# o_clone_rev_fi2.net
KiCad netlist of a schematic drawn in EAGLE
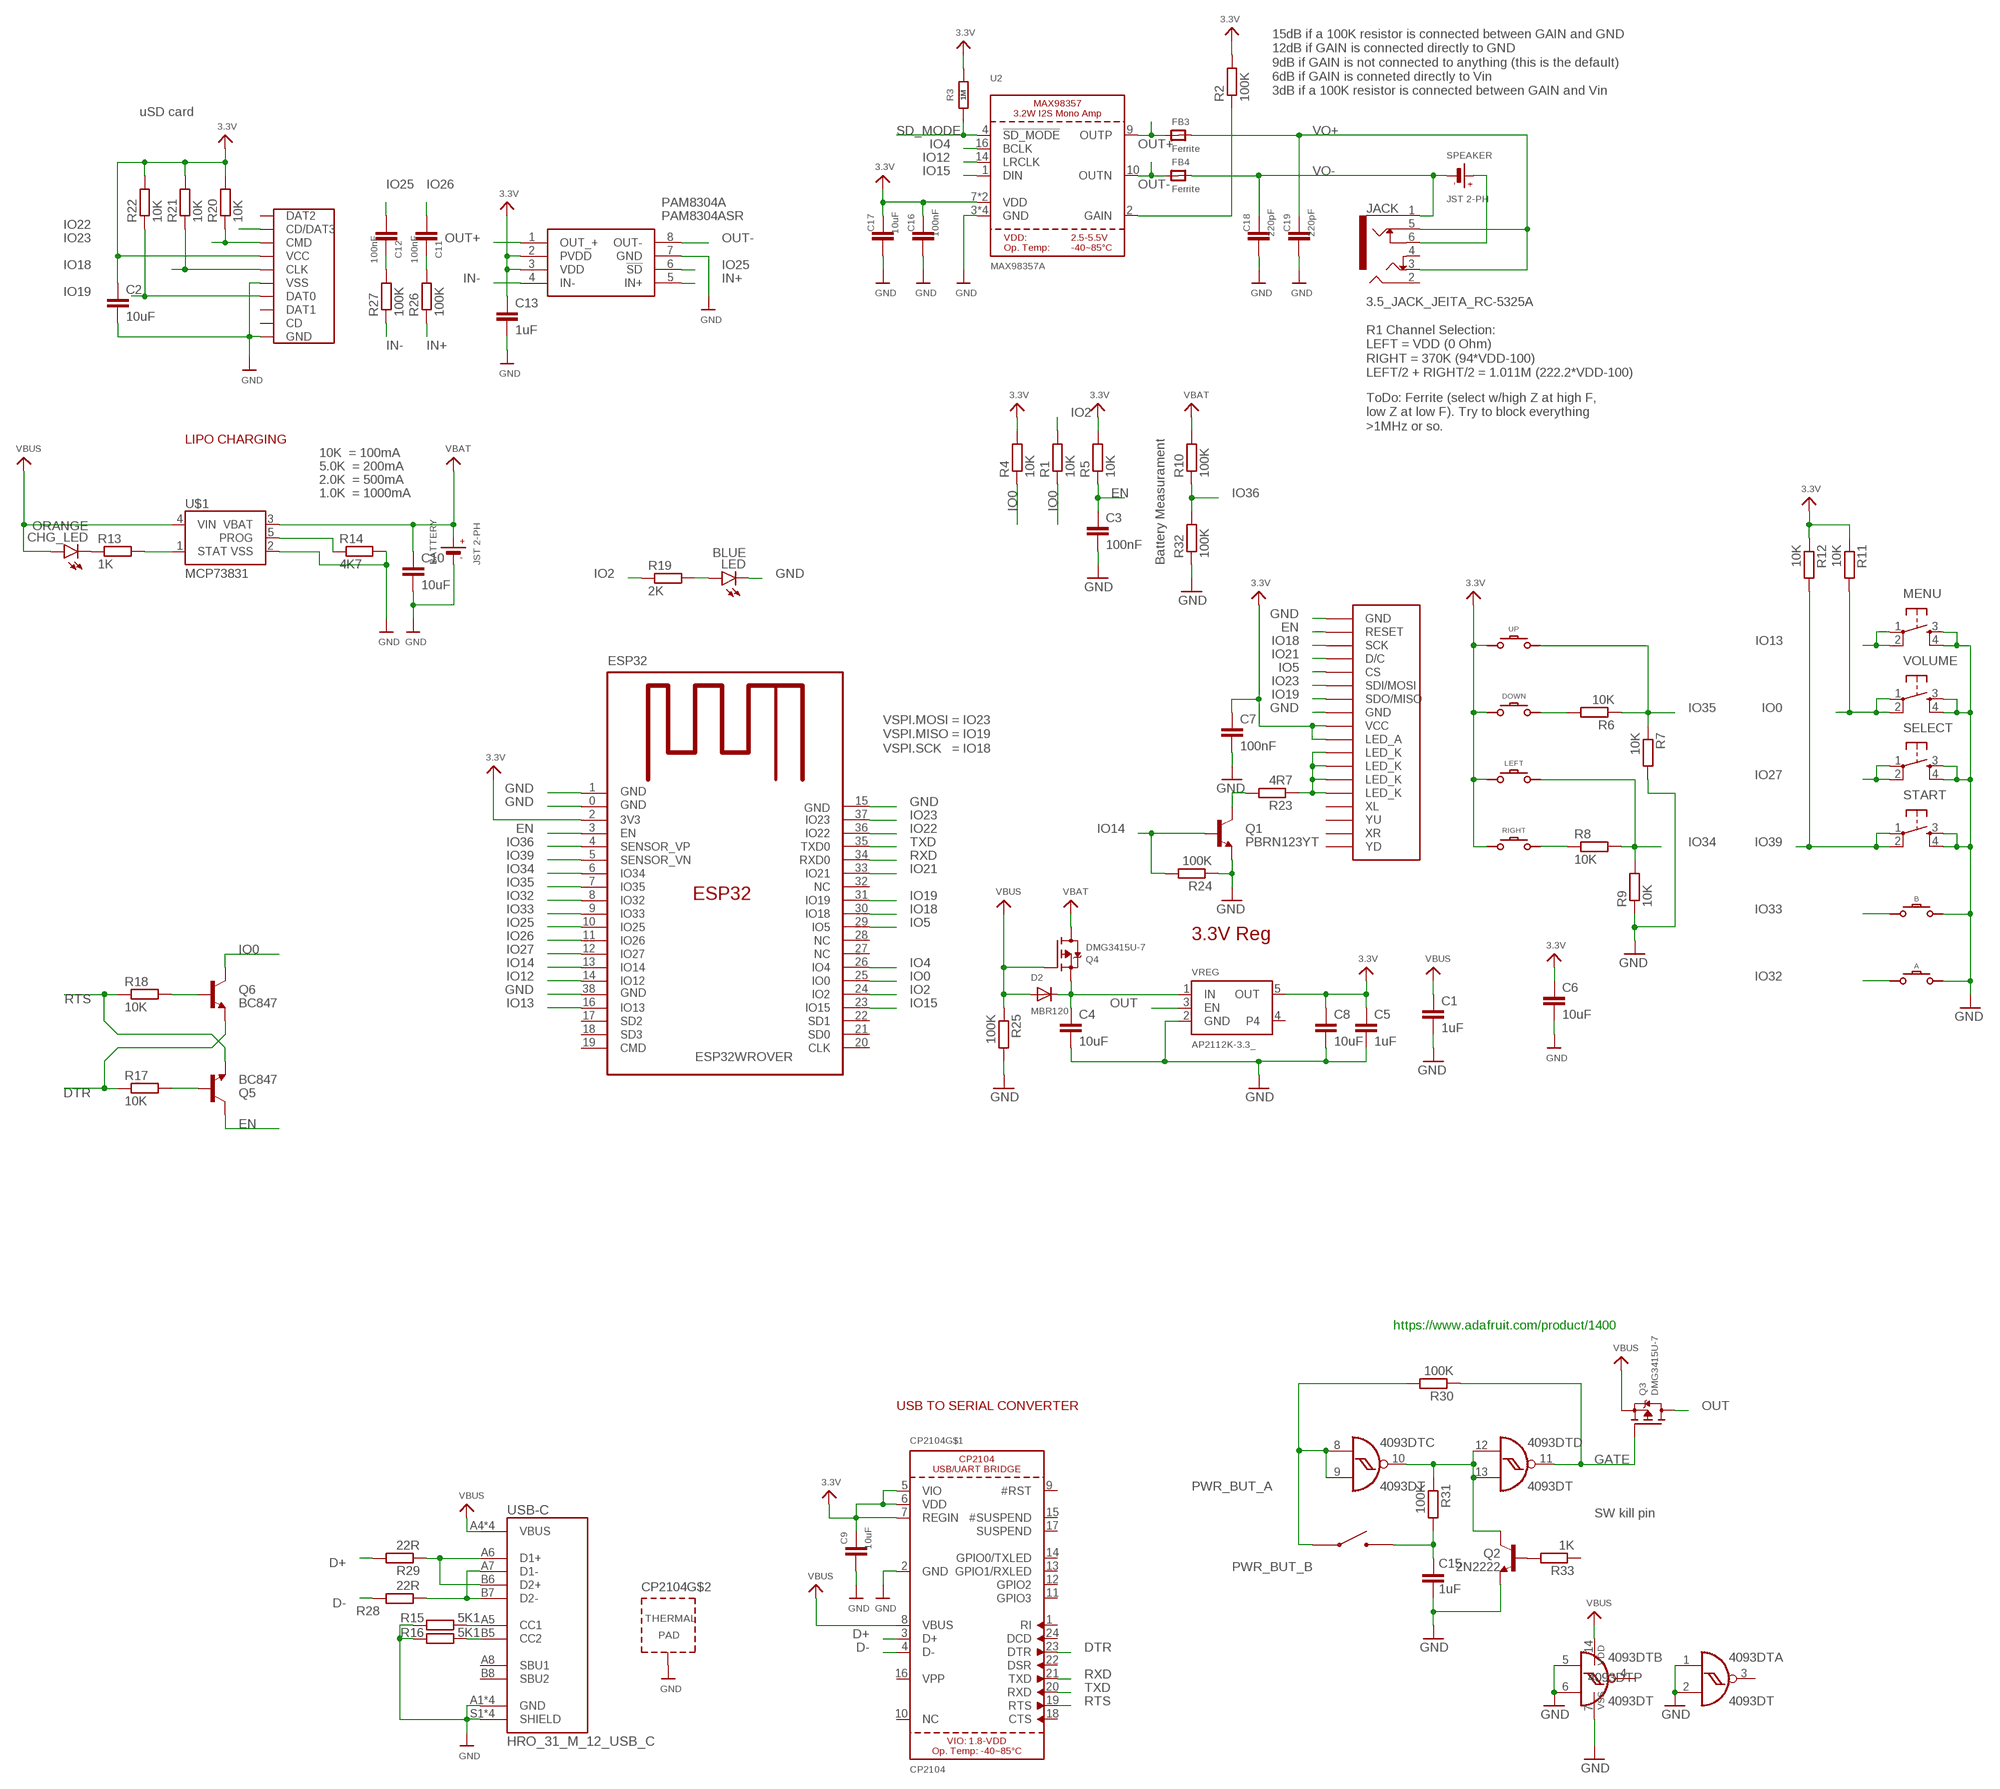
[diagram p0: schematic, sheet 1]

(export (version "E")
  (design (tool "Eeschema 10.0.6"))
  (components
    (comp (ref "4093DT")
      (value "4093DT")
      (footprint "eagle-import:MC14093B-TSSOP14")
      (libsource (lib "eagle-import") (part "4093DT"))
    )
    (comp (ref "A")
      (value "CONDUCTIVE_BUTTONCONDUCTIVE_BUTTON_THICK")
      (footprint "eagle-import:CONDUCTIVE_BUTTON_THICK")
      (libsource (lib "eagle-import") (part "CONDUCTIVE_BUTTONCONDUCTIVE_BUTTON_THICK"))
    )
    (comp (ref "B")
      (value "CONDUCTIVE_BUTTONCONDUCTIVE_BUTTON_THICK")
      (footprint "eagle-import:CONDUCTIVE_BUTTON_THICK")
      (libsource (lib "eagle-import") (part "CONDUCTIVE_BUTTONCONDUCTIVE_BUTTON_THICK"))
    )
    (comp (ref "BATTERY")
      (value "JST 2-PH")
      (footprint "eagle-import:JSTPH2")
      (libsource (lib "eagle-import") (part "JST_CONNECTOR"))
    )
    (comp (ref "C1")
      (value "1uF")
      (footprint "eagle-import:C0805")
      (libsource (lib "eagle-import") (part "C-EUC0805"))
    )
    (comp (ref "C2")
      (value "10uF")
      (footprint "eagle-import:C0805")
      (libsource (lib "eagle-import") (part "C-EUC0805"))
    )
    (comp (ref "C3")
      (value "100nF")
      (footprint "eagle-import:C0805")
      (libsource (lib "eagle-import") (part "C-EUC0805"))
    )
    (comp (ref "C4")
      (value "10uF")
      (footprint "eagle-import:C0805")
      (libsource (lib "eagle-import") (part "C-EUC0805"))
    )
    (comp (ref "C5")
      (value "1uF")
      (footprint "eagle-import:C0805")
      (libsource (lib "eagle-import") (part "C-EUC0805"))
    )
    (comp (ref "C6")
      (value "10uF")
      (footprint "eagle-import:C0805")
      (libsource (lib "eagle-import") (part "C-EUC0805"))
    )
    (comp (ref "C7")
      (value "100nF")
      (footprint "eagle-import:C0805")
      (libsource (lib "eagle-import") (part "C-EUC0805"))
    )
    (comp (ref "C8")
      (value "10uF")
      (footprint "eagle-import:C0805")
      (libsource (lib "eagle-import") (part "C-EUC0805"))
    )
    (comp (ref "C9")
      (value "10uF")
      (footprint "eagle-import:C0805")
      (libsource (lib "eagle-import") (part "C-EUC0805"))
    )
    (comp (ref "C10")
      (value "10uF")
      (footprint "eagle-import:C0805")
      (libsource (lib "eagle-import") (part "C-EUC0805"))
    )
    (comp (ref "C11")
      (value "100nF")
      (footprint "eagle-import:C0805")
      (libsource (lib "eagle-import") (part "C-EUC0805"))
    )
    (comp (ref "C12")
      (value "100nF")
      (footprint "eagle-import:C0805")
      (libsource (lib "eagle-import") (part "C-EUC0805"))
    )
    (comp (ref "C13")
      (value "1uF")
      (footprint "eagle-import:C0805")
      (libsource (lib "eagle-import") (part "C-EUC0805"))
    )
    (comp (ref "C15")
      (value "1uF")
      (footprint "eagle-import:C0805")
      (libsource (lib "eagle-import") (part "C-EUC0805"))
    )
    (comp (ref "C16")
      (value "100nF")
      (footprint "eagle-import:C0805")
      (libsource (lib "eagle-import") (part "C-EUC0805"))
    )
    (comp (ref "C17")
      (value "10uF")
      (footprint "eagle-import:C0805")
      (libsource (lib "eagle-import") (part "C-EUC0805"))
    )
    (comp (ref "C18")
      (value "220pF")
      (footprint "eagle-import:C0805")
      (libsource (lib "eagle-import") (part "C-EUC0805"))
    )
    (comp (ref "C19")
      (value "220pF")
      (footprint "eagle-import:C0805")
      (libsource (lib "eagle-import") (part "C-EUC0805"))
    )
    (comp (ref "CHG_LED")
      (value "ORANGE")
      (footprint "eagle-import:CHIPLED_0805")
      (libsource (lib "eagle-import") (part "LEDCHIPLED_0805"))
    )
    (comp (ref "CP2104")
      (value "CP2104")
      (footprint "eagle-import:QFN24_4MM_SMSC")
      (libsource (lib "eagle-import") (part "CP2104"))
    )
    (comp (ref "D2")
      (value "MBR120")
      (footprint "eagle-import:SOD-123")
      (libsource (lib "eagle-import") (part "DIODESOD-123"))
    )
    (comp (ref "DOWN")
      (value "CONDUCTIVE_BUTTONCONDUCTIVE_BUTTON_DIRECTIONAL_THICK")
      (footprint "eagle-import:CONDUCTIVE_BUTTON_DIRECTIONAL_THICK")
      (libsource (lib "eagle-import") (part "CONDUCTIVE_BUTTONCONDUCTIVE_BUTTON_DIRECTIONAL_THICK"))
    )
    (comp (ref "ESP32")
      (value "ESP32WROVER")
      (footprint "eagle-import:ESP32WROVER")
      (libsource (lib "eagle-import") (part "ESP32WROVER"))
    )
    (comp (ref "FB3")
      (value "Ferrite")
      (footprint "eagle-import:0805")
      (libsource (lib "eagle-import") (part "FERRITE0805"))
    )
    (comp (ref "FB4")
      (value "Ferrite")
      (footprint "eagle-import:0805")
      (libsource (lib "eagle-import") (part "FERRITE0805"))
    )
    (comp (ref "JACK")
      (value "3.5_JACK_JEITA_RC-5325A")
      (footprint "eagle-import:3.5_JACK_JEITA_RC-5325A")
      (libsource (lib "eagle-import") (part "3.5_JACK_JEITA_RC-5325A"))
    )
    (comp (ref "LCD")
      (value "ILI9341_3.2LCD_")
      (footprint "eagle-import:LI9341_3.2LCD")
      (libsource (lib "eagle-import") (part "ILI9341_3.2LCD_"))
    )
    (comp (ref "LED")
      (value "BLUE")
      (footprint "eagle-import:CHIPLED_0805")
      (libsource (lib "eagle-import") (part "LEDCHIPLED_0805"))
    )
    (comp (ref "LEFT")
      (value "CONDUCTIVE_BUTTONCONDUCTIVE_BUTTON_DIRECTIONAL_THICK")
      (footprint "eagle-import:CONDUCTIVE_BUTTON_DIRECTIONAL_THICK")
      (libsource (lib "eagle-import") (part "CONDUCTIVE_BUTTONCONDUCTIVE_BUTTON_DIRECTIONAL_THICK"))
    )
    (comp (ref "MENU")
      (value "TACTILE_SWITCHE_5X5_MICRO_")
      (footprint "eagle-import:TACTILE_SWITCH_5X5_MICRO")
      (libsource (lib "eagle-import") (part "TACTILE_SWITCHE_5X5_MICRO_"))
    )
    (comp (ref "PAM8304A")
      (value "PAM8304ASR")
      (footprint "eagle-import:SOP65P490X110-8N")
      (fields (field (name "MOUSER_PART_NUMBER") "621-PAM8304ASR"))
      (libsource (lib "eagle-import") (part "PAM8304ASR"))
    )
    (comp (ref "Q1")
      (value "PBRN123YT")
      (footprint "eagle-import:SOT23-3")
      (libsource (lib "eagle-import") (part "TRANSISTOR_NPNSOT23-3"))
    )
    (comp (ref "Q2")
      (value "2N2222")
      (footprint "eagle-import:SOT23-BEC")
      (libsource (lib "eagle-import") (part "-NPN-SOT23-BECMMBT2222ALT1"))
    )
    (comp (ref "Q3")
      (value "DMG3415U-7")
      (footprint "eagle-import:SOT23-WIDE")
      (libsource (lib "eagle-import") (part "MOSFET-PWIDE"))
    )
    (comp (ref "Q4")
      (value "DMG3415U-7")
      (footprint "eagle-import:SOT23-R")
      (libsource (lib "eagle-import") (part "MOSFET-P"))
    )
    (comp (ref "Q5")
      (value "BC847")
      (footprint "eagle-import:SOT23-3")
      (libsource (lib "eagle-import") (part "TRANSISTOR_NPNSOT23-3"))
    )
    (comp (ref "Q6")
      (value "BC847")
      (footprint "eagle-import:SOT23-3")
      (libsource (lib "eagle-import") (part "TRANSISTOR_NPNSOT23-3"))
    )
    (comp (ref "R1")
      (value "10K")
      (footprint "eagle-import:R0805")
      (libsource (lib "eagle-import") (part "R-EU_R0805"))
    )
    (comp (ref "R2")
      (value "100K")
      (footprint "eagle-import:R0805")
      (libsource (lib "eagle-import") (part "R-EU_R0805"))
    )
    (comp (ref "R3")
      (value "1M")
      (footprint "eagle-import:R0805")
      (libsource (lib "eagle-import") (part "R-EU_R0805"))
    )
    (comp (ref "R4")
      (value "10K")
      (footprint "eagle-import:R0805")
      (libsource (lib "eagle-import") (part "R-EU_R0805"))
    )
    (comp (ref "R5")
      (value "10K")
      (footprint "eagle-import:R0805")
      (libsource (lib "eagle-import") (part "R-EU_R0805"))
    )
    (comp (ref "R6")
      (value "10K")
      (footprint "eagle-import:R0805")
      (libsource (lib "eagle-import") (part "R-EU_R0805"))
    )
    (comp (ref "R7")
      (value "10K")
      (footprint "eagle-import:R0805")
      (libsource (lib "eagle-import") (part "R-EU_R0805"))
    )
    (comp (ref "R8")
      (value "10K")
      (footprint "eagle-import:R0805")
      (libsource (lib "eagle-import") (part "R-EU_R0805"))
    )
    (comp (ref "R9")
      (value "10K")
      (footprint "eagle-import:R0805")
      (libsource (lib "eagle-import") (part "R-EU_R0805"))
    )
    (comp (ref "R10")
      (value "100K")
      (footprint "eagle-import:R0805")
      (libsource (lib "eagle-import") (part "R-EU_R0805"))
    )
    (comp (ref "R11")
      (value "10K")
      (footprint "eagle-import:R0805")
      (libsource (lib "eagle-import") (part "R-EU_R0805"))
    )
    (comp (ref "R12")
      (value "10K")
      (footprint "eagle-import:R0805")
      (libsource (lib "eagle-import") (part "R-EU_R0805"))
    )
    (comp (ref "R13")
      (value "1K")
      (footprint "eagle-import:R0805")
      (libsource (lib "eagle-import") (part "R-EU_R0805"))
    )
    (comp (ref "R14")
      (value "4K7")
      (footprint "eagle-import:R0805")
      (libsource (lib "eagle-import") (part "R-EU_R0805"))
    )
    (comp (ref "R15")
      (value "5K1")
      (footprint "eagle-import:R0805")
      (libsource (lib "eagle-import") (part "R-EU_R0805"))
    )
    (comp (ref "R16")
      (value "5K1")
      (footprint "eagle-import:R0805")
      (libsource (lib "eagle-import") (part "R-EU_R0805"))
    )
    (comp (ref "R17")
      (value "10K")
      (footprint "eagle-import:R0805")
      (libsource (lib "eagle-import") (part "R-EU_R0805"))
    )
    (comp (ref "R18")
      (value "10K")
      (footprint "eagle-import:R0805")
      (libsource (lib "eagle-import") (part "R-EU_R0805"))
    )
    (comp (ref "R19")
      (value "2K")
      (footprint "eagle-import:R0805")
      (libsource (lib "eagle-import") (part "R-EU_R0805"))
    )
    (comp (ref "R20")
      (value "10K")
      (footprint "eagle-import:R0805")
      (libsource (lib "eagle-import") (part "R-EU_R0805"))
    )
    (comp (ref "R21")
      (value "10K")
      (footprint "eagle-import:R0805")
      (libsource (lib "eagle-import") (part "R-EU_R0805"))
    )
    (comp (ref "R22")
      (value "10K")
      (footprint "eagle-import:R0805")
      (libsource (lib "eagle-import") (part "R-EU_R0805"))
    )
    (comp (ref "R23")
      (value "4R7")
      (footprint "eagle-import:R0805")
      (libsource (lib "eagle-import") (part "R-EU_R0805"))
    )
    (comp (ref "R24")
      (value "100K")
      (footprint "eagle-import:R0805")
      (libsource (lib "eagle-import") (part "R-EU_R0805"))
    )
    (comp (ref "R25")
      (value "100K")
      (footprint "eagle-import:R0805")
      (libsource (lib "eagle-import") (part "R-EU_R0805"))
    )
    (comp (ref "R26")
      (value "100K")
      (footprint "eagle-import:R0805")
      (libsource (lib "eagle-import") (part "R-EU_R0805"))
    )
    (comp (ref "R27")
      (value "100K")
      (footprint "eagle-import:R0805")
      (libsource (lib "eagle-import") (part "R-EU_R0805"))
    )
    (comp (ref "R28")
      (value "22R")
      (footprint "eagle-import:R0805")
      (libsource (lib "eagle-import") (part "R-EU_R0805"))
    )
    (comp (ref "R29")
      (value "22R")
      (footprint "eagle-import:R0805")
      (libsource (lib "eagle-import") (part "R-EU_R0805"))
    )
    (comp (ref "R30")
      (value "100K")
      (footprint "eagle-import:R0805")
      (libsource (lib "eagle-import") (part "R-EU_R0805"))
    )
    (comp (ref "R31")
      (value "100K")
      (footprint "eagle-import:R0805")
      (libsource (lib "eagle-import") (part "R-EU_R0805"))
    )
    (comp (ref "R32")
      (value "100K")
      (footprint "eagle-import:R0805")
      (libsource (lib "eagle-import") (part "R-EU_R0805"))
    )
    (comp (ref "R33")
      (value "1K")
      (footprint "eagle-import:R0805")
      (libsource (lib "eagle-import") (part "R-EU_R0805"))
    )
    (comp (ref "RIGHT")
      (value "CONDUCTIVE_BUTTONCONDUCTIVE_BUTTON_DIRECTIONAL_THICK")
      (footprint "eagle-import:CONDUCTIVE_BUTTON_DIRECTIONAL_THICK")
      (libsource (lib "eagle-import") (part "CONDUCTIVE_BUTTONCONDUCTIVE_BUTTON_DIRECTIONAL_THICK"))
    )
    (comp (ref "S2")
      (value "TL3330AF130QG")
      (footprint "eagle-import:TL3330AF130QG")
      (fields (field (name "MOUSER_PART_NUMBER") "612-TL3330AF130QG"))
      (libsource (lib "eagle-import") (part "TL3330AF130QG"))
    )
    (comp (ref "SD_CARD")
      (value "MICRO_SD_CARD_")
      (footprint "eagle-import:TFP09-2--12B")
      (libsource (lib "eagle-import") (part "MICRO_SD_CARD_"))
    )
    (comp (ref "SELECT")
      (value "TACTILE_SWITCHE_5X5_MICRO_")
      (footprint "eagle-import:TACTILE_SWITCH_5X5_MICRO")
      (libsource (lib "eagle-import") (part "TACTILE_SWITCHE_5X5_MICRO_"))
    )
    (comp (ref "SPEAKER")
      (value "JST 2-PH")
      (footprint "eagle-import:JSTPH2")
      (libsource (lib "eagle-import") (part "JST_CONNECTOR"))
    )
    (comp (ref "START")
      (value "TACTILE_SWITCHE_5X5_MICRO_")
      (footprint "eagle-import:TACTILE_SWITCH_5X5_MICRO")
      (libsource (lib "eagle-import") (part "TACTILE_SWITCHE_5X5_MICRO_"))
    )
    (comp (ref "U$1")
      (value "MCP73831")
      (footprint "eagle-import:SOT95P290X120-5")
      (libsource (lib "eagle-import") (part "MCP73831"))
    )
    (comp (ref "U2")
      (value "MAX98357A")
      (footprint "eagle-import:QFN16_3MM")
      (libsource (lib "eagle-import") (part "AUDIOAMP_MAX98357"))
    )
    (comp (ref "UP")
      (value "CONDUCTIVE_BUTTONCONDUCTIVE_BUTTON_DIRECTIONAL_THICK")
      (footprint "eagle-import:CONDUCTIVE_BUTTON_DIRECTIONAL_THICK")
      (libsource (lib "eagle-import") (part "CONDUCTIVE_BUTTONCONDUCTIVE_BUTTON_DIRECTIONAL_THICK"))
    )
    (comp (ref "USB-C")
      (value "HRO_31_M_12_USB_C")
      (footprint "eagle-import:HRO_31_M_12_USB_C")
      (libsource (lib "eagle-import") (part "HRO_31_M_12_USB_C"))
    )
    (comp (ref "VOLUME")
      (value "TACTILE_SWITCHE_5X5_MICRO_")
      (footprint "eagle-import:TACTILE_SWITCH_5X5_MICRO")
      (libsource (lib "eagle-import") (part "TACTILE_SWITCHE_5X5_MICRO_"))
    )
    (comp (ref "VREG")
      (value "AP2112K-3.3_")
      (footprint "eagle-import:SOT95P290X120-5")
      (libsource (lib "eagle-import") (part "AP2112K-3.3_"))
    )
  )
  (nets
    (net (code "1") (name "/D+") (class "Default")
      (node (ref "CP2104") (pin "3") (pinfunction "D+_3") (pintype "bidirectional"))
      (node (ref "R29") (pin "2") (pinfunction "2_2") (pintype "passive"))
    )
    (net (code "2") (name "/D-") (class "Default")
      (node (ref "CP2104") (pin "4") (pinfunction "D-_4") (pintype "bidirectional"))
      (node (ref "R28") (pin "2") (pinfunction "2_2") (pintype "passive"))
    )
    (net (code "3") (name "/DTR") (class "Default")
      (node (ref "CP2104") (pin "23") (pinfunction "DTR_23") (pintype "output"))
      (node (ref "Q6") (pin "2") (pinfunction "E_2") (pintype "passive"))
      (node (ref "R17") (pin "1") (pinfunction "1_1") (pintype "passive"))
    )
    (net (code "4") (name "/EN") (class "Default")
      (node (ref "C3") (pin "1") (pinfunction "1_1") (pintype "passive"))
      (node (ref "ESP32") (pin "3") (pinfunction "EN_3") (pintype "bidirectional"))
      (node (ref "LCD") (pin "P$2") (pinfunction "RESET_P$2") (pintype "bidirectional"))
      (node (ref "Q5") (pin "3") (pinfunction "C_3") (pintype "passive"))
      (node (ref "R5") (pin "1") (pinfunction "1_1") (pintype "passive"))
    )
    (net (code "5") (name "/GATE") (class "Default")
      (node (ref "4093DT") (pin "11") (pinfunction "O_11") (pintype "output"))
      (node (ref "Q3") (pin "1") (pinfunction "G_1") (pintype "passive"))
      (node (ref "R30") (pin "1") (pinfunction "1_1") (pintype "passive"))
    )
    (net (code "6") (name "/IN+") (class "Default")
      (node (ref "PAM8304A") (pin "5") (pinfunction "IN+_5") (pintype "bidirectional"))
      (node (ref "R26") (pin "1") (pinfunction "1_1") (pintype "passive"))
    )
    (net (code "7") (name "/IN-") (class "Default")
      (node (ref "PAM8304A") (pin "4") (pinfunction "IN-_4") (pintype "bidirectional"))
      (node (ref "R27") (pin "1") (pinfunction "1_1") (pintype "passive"))
    )
    (net (code "8") (name "/IO0") (class "Default")
      (node (ref "ESP32") (pin "25") (pinfunction "IO0_25") (pintype "bidirectional"))
      (node (ref "Q6") (pin "3") (pinfunction "C_3") (pintype "passive"))
      (node (ref "R1") (pin "1") (pinfunction "1_1") (pintype "passive"))
      (node (ref "R11") (pin "2") (pinfunction "2_2") (pintype "passive"))
      (node (ref "R4") (pin "1") (pinfunction "1_1") (pintype "passive"))
      (node (ref "VOLUME") (pin "1") (pinfunction "1_1") (pintype "passive"))
      (node (ref "VOLUME") (pin "2") (pinfunction "2_2") (pintype "passive"))
    )
    (net (code "9") (name "/IO2") (class "Default")
      (node (ref "ESP32") (pin "24") (pinfunction "IO2_24") (pintype "bidirectional"))
      (node (ref "R1") (pin "2") (pinfunction "2_2") (pintype "passive"))
      (node (ref "R19") (pin "1") (pinfunction "1_1") (pintype "passive"))
    )
    (net (code "10") (name "/IO4") (class "Default")
      (node (ref "ESP32") (pin "26") (pinfunction "IO4_26") (pintype "bidirectional"))
      (node (ref "U2") (pin "16") (pinfunction "BCLK_16") (pintype "bidirectional"))
    )
    (net (code "11") (name "/IO5") (class "Default")
      (node (ref "ESP32") (pin "29") (pinfunction "IO5_29") (pintype "bidirectional"))
      (node (ref "LCD") (pin "P$5") (pinfunction "CS_P$5") (pintype "bidirectional"))
    )
    (net (code "12") (name "/IO12") (class "Default")
      (node (ref "ESP32") (pin "14") (pinfunction "IO12_14") (pintype "bidirectional"))
      (node (ref "U2") (pin "14") (pinfunction "LRCLK_14") (pintype "bidirectional"))
    )
    (net (code "13") (name "/IO13") (class "Default")
      (node (ref "ESP32") (pin "16") (pinfunction "IO13_16") (pintype "bidirectional"))
      (node (ref "MENU") (pin "1") (pinfunction "1_1") (pintype "passive"))
      (node (ref "MENU") (pin "2") (pinfunction "2_2") (pintype "passive"))
    )
    (net (code "14") (name "/IO14") (class "Default")
      (node (ref "ESP32") (pin "13") (pinfunction "IO14_13") (pintype "bidirectional"))
      (node (ref "Q1") (pin "1") (pinfunction "B_1") (pintype "passive"))
      (node (ref "R24") (pin "2") (pinfunction "2_2") (pintype "passive"))
    )
    (net (code "15") (name "/IO15") (class "Default")
      (node (ref "ESP32") (pin "23") (pinfunction "IO15_23") (pintype "bidirectional"))
      (node (ref "U2") (pin "1") (pinfunction "DIN_1") (pintype "bidirectional"))
    )
    (net (code "16") (name "/IO18") (class "Default")
      (node (ref "ESP32") (pin "30") (pinfunction "IO18_30") (pintype "bidirectional"))
      (node (ref "LCD") (pin "P$3") (pinfunction "SCK_P$3") (pintype "bidirectional"))
      (node (ref "R21") (pin "1") (pinfunction "1_1") (pintype "passive"))
      (node (ref "SD_CARD") (pin "CLK") (pinfunction "CLK_CLK") (pintype "bidirectional"))
    )
    (net (code "17") (name "/IO19") (class "Default")
      (node (ref "ESP32") (pin "31") (pinfunction "IO19_31") (pintype "bidirectional"))
      (node (ref "LCD") (pin "P$7") (pinfunction "SDO/MISO_P$7") (pintype "bidirectional"))
      (node (ref "R22") (pin "1") (pinfunction "1_1") (pintype "passive"))
      (node (ref "SD_CARD") (pin "DAT0") (pinfunction "DAT0_DAT0") (pintype "bidirectional"))
    )
    (net (code "18") (name "/IO21") (class "Default")
      (node (ref "ESP32") (pin "33") (pinfunction "IO21_33") (pintype "bidirectional"))
      (node (ref "LCD") (pin "P$4") (pinfunction "D/C_P$4") (pintype "bidirectional"))
    )
    (net (code "19") (name "/IO22") (class "Default")
      (node (ref "ESP32") (pin "36") (pinfunction "IO22_36") (pintype "bidirectional"))
      (node (ref "SD_CARD") (pin "CD/DAT3") (pinfunction "CD/DAT3_CD/DAT3") (pintype "bidirectional"))
    )
    (net (code "20") (name "/IO23") (class "Default")
      (node (ref "ESP32") (pin "37") (pinfunction "IO23_37") (pintype "bidirectional"))
      (node (ref "LCD") (pin "P$6") (pinfunction "SDI/MOSI_P$6") (pintype "bidirectional"))
      (node (ref "R20") (pin "1") (pinfunction "1_1") (pintype "passive"))
      (node (ref "SD_CARD") (pin "CMD") (pinfunction "CMD_CMD") (pintype "bidirectional"))
    )
    (net (code "21") (name "/IO25") (class "Default")
      (node (ref "C12") (pin "2") (pinfunction "2_2") (pintype "passive"))
      (node (ref "ESP32") (pin "10") (pinfunction "IO25_10") (pintype "bidirectional"))
      (node (ref "PAM8304A") (pin "6") (pinfunction "~{SD}_6") (pintype "bidirectional"))
    )
    (net (code "22") (name "/IO26") (class "Default")
      (node (ref "C11") (pin "2") (pinfunction "2_2") (pintype "passive"))
      (node (ref "ESP32") (pin "11") (pinfunction "IO26_11") (pintype "bidirectional"))
    )
    (net (code "23") (name "/IO27") (class "Default")
      (node (ref "ESP32") (pin "12") (pinfunction "IO27_12") (pintype "bidirectional"))
      (node (ref "SELECT") (pin "1") (pinfunction "1_1") (pintype "passive"))
      (node (ref "SELECT") (pin "2") (pinfunction "2_2") (pintype "passive"))
    )
    (net (code "24") (name "/IO32") (class "Default")
      (node (ref "A") (pin "P$GND") (pinfunction "P$GND_P$GND") (pintype "bidirectional"))
      (node (ref "ESP32") (pin "8") (pinfunction "IO32_8") (pintype "bidirectional"))
    )
    (net (code "25") (name "/IO33") (class "Default")
      (node (ref "B") (pin "P$GND") (pinfunction "P$GND_P$GND") (pintype "bidirectional"))
      (node (ref "ESP32") (pin "9") (pinfunction "IO33_9") (pintype "bidirectional"))
    )
    (net (code "26") (name "/IO34") (class "Default")
      (node (ref "ESP32") (pin "6") (pinfunction "IO34_6") (pintype "bidirectional"))
      (node (ref "LEFT") (pin "P$ACTIVE") (pinfunction "P$ACTIVE_P$ACTIVE") (pintype "bidirectional"))
      (node (ref "R8") (pin "2") (pinfunction "2_2") (pintype "passive"))
      (node (ref "R9") (pin "2") (pinfunction "2_2") (pintype "passive"))
    )
    (net (code "27") (name "/IO35") (class "Default")
      (node (ref "ESP32") (pin "7") (pinfunction "IO35_7") (pintype "bidirectional"))
      (node (ref "R6") (pin "1") (pinfunction "1_1") (pintype "passive"))
      (node (ref "R7") (pin "1") (pinfunction "1_1") (pintype "passive"))
      (node (ref "UP") (pin "P$ACTIVE") (pinfunction "P$ACTIVE_P$ACTIVE") (pintype "bidirectional"))
    )
    (net (code "28") (name "/IO36") (class "Default")
      (node (ref "ESP32") (pin "4") (pinfunction "SENSOR_VP_4") (pintype "bidirectional"))
      (node (ref "R10") (pin "1") (pinfunction "1_1") (pintype "passive"))
      (node (ref "R32") (pin "2") (pinfunction "2_2") (pintype "passive"))
    )
    (net (code "29") (name "/IO39") (class "Default")
      (node (ref "ESP32") (pin "5") (pinfunction "SENSOR_VN_5") (pintype "bidirectional"))
      (node (ref "R12") (pin "2") (pinfunction "2_2") (pintype "passive"))
      (node (ref "START") (pin "1") (pinfunction "1_1") (pintype "passive"))
      (node (ref "START") (pin "2") (pinfunction "2_2") (pintype "passive"))
    )
    (net (code "30") (name "/OUT") (class "Default")
      (node (ref "Q3") (pin "3") (pinfunction "D_3") (pintype "passive"))
      (node (ref "VREG") (pin "3") (pinfunction "EN_3") (pintype "bidirectional"))
    )
    (net (code "31") (name "/OUT+") (class "Default")
      (node (ref "FB3") (pin "1") (pinfunction "P$1_1") (pintype "passive"))
      (node (ref "PAM8304A") (pin "1") (pinfunction "OUT_+_1") (pintype "bidirectional"))
      (node (ref "U2") (pin "9") (pinfunction "OUTP_9") (pintype "output"))
    )
    (net (code "32") (name "/OUT-") (class "Default")
      (node (ref "FB4") (pin "1") (pinfunction "P$1_1") (pintype "passive"))
      (node (ref "PAM8304A") (pin "8") (pinfunction "OUT-_8") (pintype "bidirectional"))
      (node (ref "U2") (pin "10") (pinfunction "OUTN_10") (pintype "output"))
    )
    (net (code "33") (name "/PWR_BUT_A") (class "Default")
      (node (ref "4093DT") (pin "8") (pinfunction "I0_8") (pintype "input"))
      (node (ref "4093DT") (pin "9") (pinfunction "I1_9") (pintype "input"))
      (node (ref "R30") (pin "2") (pinfunction "2_2") (pintype "passive"))
      (node (ref "S2") (pin "1") (pinfunction "P$1_1") (pintype "bidirectional"))
    )
    (net (code "34") (name "/PWR_BUT_B") (class "Default")
      (node (ref "C15") (pin "1") (pinfunction "1_1") (pintype "passive"))
      (node (ref "R31") (pin "2") (pinfunction "2_2") (pintype "passive"))
      (node (ref "S2") (pin "2") (pinfunction "P$2_2") (pintype "bidirectional"))
    )
    (net (code "35") (name "/RTS") (class "Default")
      (node (ref "CP2104") (pin "19") (pinfunction "RTS_19") (pintype "output"))
      (node (ref "Q5") (pin "2") (pinfunction "E_2") (pintype "passive"))
      (node (ref "R18") (pin "1") (pinfunction "1_1") (pintype "passive"))
    )
    (net (code "36") (name "/RXD") (class "Default")
      (node (ref "CP2104") (pin "21") (pinfunction "TXD_21") (pintype "output"))
      (node (ref "ESP32") (pin "34") (pinfunction "RXD0_34") (pintype "bidirectional"))
    )
    (net (code "37") (name "/SD_MODE") (class "Default")
      (node (ref "R3") (pin "1") (pinfunction "1_1") (pintype "passive"))
      (node (ref "U2") (pin "4") (pinfunction "~{SD_MODE}_4") (pintype "bidirectional"))
    )
    (net (code "38") (name "/TXD") (class "Default")
      (node (ref "CP2104") (pin "20") (pinfunction "RXD_20") (pintype "input"))
      (node (ref "ESP32") (pin "35") (pinfunction "TXD0_35") (pintype "bidirectional"))
    )
    (net (code "39") (name "/VO+") (class "Default")
      (node (ref "C19") (pin "1") (pinfunction "1_1") (pintype "passive"))
      (node (ref "FB3") (pin "2") (pinfunction "P$2_2") (pintype "passive"))
      (node (ref "JACK") (pin "3") (pinfunction "3_3") (pintype "bidirectional"))
      (node (ref "JACK") (pin "5") (pinfunction "5_5") (pintype "bidirectional"))
    )
    (net (code "40") (name "/VO-") (class "Default")
      (node (ref "C18") (pin "1") (pinfunction "1_1") (pintype "passive"))
      (node (ref "FB4") (pin "2") (pinfunction "P$2_2") (pintype "passive"))
      (node (ref "JACK") (pin "1") (pinfunction "1_1") (pintype "bidirectional"))
      (node (ref "SPEAKER") (pin "1") (pinfunction "-_1") (pintype "passive"))
    )
    (net (code "41") (name "3.3V") (class "Default")
      (node (ref "C13") (pin "1") (pinfunction "1_1") (pintype "passive"))
      (node (ref "C16") (pin "1") (pinfunction "1_1") (pintype "passive"))
      (node (ref "C17") (pin "1") (pinfunction "1_1") (pintype "passive"))
      (node (ref "C2") (pin "1") (pinfunction "1_1") (pintype "passive"))
      (node (ref "C5") (pin "1") (pinfunction "1_1") (pintype "passive"))
      (node (ref "C6") (pin "1") (pinfunction "1_1") (pintype "passive"))
      (node (ref "C7") (pin "1") (pinfunction "1_1") (pintype "passive"))
      (node (ref "C8") (pin "1") (pinfunction "1_1") (pintype "passive"))
      (node (ref "C9") (pin "1") (pinfunction "1_1") (pintype "passive"))
      (node (ref "CP2104") (pin "5") (pinfunction "VIO_5") (pintype "power_in"))
      (node (ref "CP2104") (pin "6") (pinfunction "VDD_6") (pintype "power_in"))
      (node (ref "CP2104") (pin "7") (pinfunction "REGIN_7") (pintype "power_in"))
      (node (ref "DOWN") (pin "P$GND") (pinfunction "P$GND_P$GND") (pintype "bidirectional"))
      (node (ref "ESP32") (pin "2") (pinfunction "3V3_2") (pintype "power_in"))
      (node (ref "LCD") (pin "P$10") (pinfunction "LED_A_P$10") (pintype "bidirectional"))
      (node (ref "LCD") (pin "P$9") (pinfunction "VCC_P$9") (pintype "bidirectional"))
      (node (ref "LEFT") (pin "P$GND") (pinfunction "P$GND_P$GND") (pintype "bidirectional"))
      (node (ref "PAM8304A") (pin "2") (pinfunction "PVDD_2") (pintype "bidirectional"))
      (node (ref "PAM8304A") (pin "3") (pinfunction "VDD_3") (pintype "bidirectional"))
      (node (ref "R11") (pin "1") (pinfunction "1_1") (pintype "passive"))
      (node (ref "R12") (pin "1") (pinfunction "1_1") (pintype "passive"))
      (node (ref "R2") (pin "2") (pinfunction "2_2") (pintype "passive"))
      (node (ref "R20") (pin "2") (pinfunction "2_2") (pintype "passive"))
      (node (ref "R21") (pin "2") (pinfunction "2_2") (pintype "passive"))
      (node (ref "R22") (pin "2") (pinfunction "2_2") (pintype "passive"))
      (node (ref "R3") (pin "2") (pinfunction "2_2") (pintype "passive"))
      (node (ref "R4") (pin "2") (pinfunction "2_2") (pintype "passive"))
      (node (ref "R5") (pin "2") (pinfunction "2_2") (pintype "passive"))
      (node (ref "RIGHT") (pin "P$GND") (pinfunction "P$GND_P$GND") (pintype "bidirectional"))
      (node (ref "SD_CARD") (pin "VCC") (pinfunction "VCC_VCC") (pintype "bidirectional"))
      (node (ref "U2") (pin "7") (pinfunction "VDD_7") (pintype "power_in"))
      (node (ref "U2") (pin "8") (pinfunction "VDD_8") (pintype "power_in"))
      (node (ref "UP") (pin "P$GND") (pinfunction "P$GND_P$GND") (pintype "bidirectional"))
      (node (ref "VREG") (pin "5") (pinfunction "OUT_5") (pintype "bidirectional"))
    )
    (net (code "42") (name "GND") (class "Default")
      (node (ref "4093DT") (pin "1") (pinfunction "I0_1") (pintype "input"))
      (node (ref "4093DT") (pin "2") (pinfunction "I1_2") (pintype "input"))
      (node (ref "4093DT") (pin "5") (pinfunction "I0_5") (pintype "input"))
      (node (ref "4093DT") (pin "6") (pinfunction "I1_6") (pintype "input"))
      (node (ref "4093DT") (pin "7") (pinfunction "VSS_7") (pintype "power_in"))
      (node (ref "A") (pin "P$ACTIVE") (pinfunction "P$ACTIVE_P$ACTIVE") (pintype "bidirectional"))
      (node (ref "B") (pin "P$ACTIVE") (pinfunction "P$ACTIVE_P$ACTIVE") (pintype "bidirectional"))
      (node (ref "BATTERY") (pin "1") (pinfunction "-_1") (pintype "passive"))
      (node (ref "C1") (pin "2") (pinfunction "2_2") (pintype "passive"))
      (node (ref "C10") (pin "2") (pinfunction "2_2") (pintype "passive"))
      (node (ref "C13") (pin "2") (pinfunction "2_2") (pintype "passive"))
      (node (ref "C15") (pin "2") (pinfunction "2_2") (pintype "passive"))
      (node (ref "C16") (pin "2") (pinfunction "2_2") (pintype "passive"))
      (node (ref "C17") (pin "2") (pinfunction "2_2") (pintype "passive"))
      (node (ref "C18") (pin "2") (pinfunction "2_2") (pintype "passive"))
      (node (ref "C19") (pin "2") (pinfunction "2_2") (pintype "passive"))
      (node (ref "C2") (pin "2") (pinfunction "2_2") (pintype "passive"))
      (node (ref "C3") (pin "2") (pinfunction "2_2") (pintype "passive"))
      (node (ref "C4") (pin "2") (pinfunction "2_2") (pintype "passive"))
      (node (ref "C5") (pin "2") (pinfunction "2_2") (pintype "passive"))
      (node (ref "C6") (pin "2") (pinfunction "2_2") (pintype "passive"))
      (node (ref "C7") (pin "2") (pinfunction "2_2") (pintype "passive"))
      (node (ref "C8") (pin "2") (pinfunction "2_2") (pintype "passive"))
      (node (ref "C9") (pin "2") (pinfunction "2_2") (pintype "passive"))
      (node (ref "CP2104") (pin "2") (pinfunction "GND_2") (pintype "power_in"))
      (node (ref "CP2104") (pin "THERM") (pinfunction "TP_THERM") (pintype "power_in"))
      (node (ref "ESP32") (pin "0") (pinfunction "GND_0") (pintype "power_in"))
      (node (ref "ESP32") (pin "1") (pinfunction "GND_1") (pintype "power_in"))
      (node (ref "ESP32") (pin "15") (pinfunction "GND_15") (pintype "power_in"))
      (node (ref "ESP32") (pin "38") (pinfunction "GND_38") (pintype "power_in"))
      (node (ref "LCD") (pin "P$1") (pinfunction "GND_P$1") (pintype "bidirectional"))
      (node (ref "LCD") (pin "P$8") (pinfunction "GND_P$8") (pintype "bidirectional"))
      (node (ref "LED") (pin "C") (pinfunction "C_C") (pintype "passive"))
      (node (ref "MENU") (pin "3") (pinfunction "3_3") (pintype "passive"))
      (node (ref "MENU") (pin "4") (pinfunction "4_4") (pintype "passive"))
      (node (ref "PAM8304A") (pin "7") (pinfunction "GND_7") (pintype "bidirectional"))
      (node (ref "Q1") (pin "2") (pinfunction "E_2") (pintype "passive"))
      (node (ref "Q2") (pin "E") (pinfunction "E_E") (pintype "passive"))
      (node (ref "R14") (pin "2") (pinfunction "2_2") (pintype "passive"))
      (node (ref "R15") (pin "2") (pinfunction "2_2") (pintype "passive"))
      (node (ref "R16") (pin "2") (pinfunction "2_2") (pintype "passive"))
      (node (ref "R24") (pin "1") (pinfunction "1_1") (pintype "passive"))
      (node (ref "R25") (pin "2") (pinfunction "2_2") (pintype "passive"))
      (node (ref "R32") (pin "1") (pinfunction "1_1") (pintype "passive"))
      (node (ref "R7") (pin "2") (pinfunction "2_2") (pintype "passive"))
      (node (ref "R9") (pin "1") (pinfunction "1_1") (pintype "passive"))
      (node (ref "SD_CARD") (pin "GND") (pinfunction "GND_GND") (pintype "bidirectional"))
      (node (ref "SD_CARD") (pin "GND@1") (pinfunction "GND_GND@1") (pintype "bidirectional"))
      (node (ref "SD_CARD") (pin "GND@2") (pinfunction "GND_GND@2") (pintype "bidirectional"))
      (node (ref "SD_CARD") (pin "GND@3") (pinfunction "VSS_GND@3") (pintype "bidirectional"))
      (node (ref "SD_CARD") (pin "VSS") (pinfunction "GND_VSS") (pintype "bidirectional"))
      (node (ref "SELECT") (pin "3") (pinfunction "3_3") (pintype "passive"))
      (node (ref "SELECT") (pin "4") (pinfunction "4_4") (pintype "passive"))
      (node (ref "START") (pin "3") (pinfunction "3_3") (pintype "passive"))
      (node (ref "START") (pin "4") (pinfunction "4_4") (pintype "passive"))
      (node (ref "U$1") (pin "2") (pinfunction "VSS_2") (pintype "power_in"))
      (node (ref "U2") (pin "11") (pinfunction "GND_11") (pintype "power_in"))
      (node (ref "U2") (pin "15") (pinfunction "GND_15") (pintype "power_in"))
      (node (ref "U2") (pin "3") (pinfunction "GND_3") (pintype "power_in"))
      (node (ref "U2") (pin "THERMAL") (pinfunction "GND_THERMAL") (pintype "power_in"))
      (node (ref "USB-C") (pin "A1") (pinfunction "GND_A1") (pintype "passive"))
      (node (ref "USB-C") (pin "A12") (pinfunction "GND_A12") (pintype "passive"))
      (node (ref "USB-C") (pin "B1") (pinfunction "GND_B1") (pintype "passive"))
      (node (ref "USB-C") (pin "B12") (pinfunction "GND_B12") (pintype "passive"))
      (node (ref "USB-C") (pin "S1") (pinfunction "SHIELD_S1") (pintype "passive"))
      (node (ref "USB-C") (pin "S2") (pinfunction "SHIELD_S2") (pintype "passive"))
      (node (ref "USB-C") (pin "S3") (pinfunction "SHIELD_S3") (pintype "passive"))
      (node (ref "USB-C") (pin "S4") (pinfunction "SHIELD_S4") (pintype "passive"))
      (node (ref "VOLUME") (pin "3") (pinfunction "3_3") (pintype "passive"))
      (node (ref "VOLUME") (pin "4") (pinfunction "4_4") (pintype "passive"))
      (node (ref "VREG") (pin "2") (pinfunction "GND_2") (pintype "bidirectional"))
    )
    (net (code "43") (name "Net-(4093DTC-O)") (class "Default")
      (node (ref "4093DT") (pin "10") (pinfunction "O_10") (pintype "output"))
      (node (ref "4093DT") (pin "12") (pinfunction "I0_12") (pintype "input"))
      (node (ref "4093DT") (pin "13") (pinfunction "I1_13") (pintype "input"))
      (node (ref "Q2") (pin "C") (pinfunction "C_C") (pintype "passive"))
      (node (ref "R31") (pin "1") (pinfunction "1_1") (pintype "passive"))
    )
    (net (code "44") (name "Net-(C11-Pad1)") (class "Default")
      (node (ref "C11") (pin "1") (pinfunction "1_1") (pintype "passive"))
      (node (ref "R26") (pin "2") (pinfunction "2_2") (pintype "passive"))
    )
    (net (code "45") (name "Net-(C12-Pad1)") (class "Default")
      (node (ref "C12") (pin "1") (pinfunction "1_1") (pintype "passive"))
      (node (ref "R27") (pin "2") (pinfunction "2_2") (pintype "passive"))
    )
    (net (code "46") (name "Net-(CHG_LED-PadC)") (class "Default")
      (node (ref "CHG_LED") (pin "C") (pinfunction "C_C") (pintype "passive"))
      (node (ref "R13") (pin "1") (pinfunction "1_1") (pintype "passive"))
    )
    (net (code "47") (name "Net-(DOWN-PadP$ACTIVE)") (class "Default")
      (node (ref "DOWN") (pin "P$ACTIVE") (pinfunction "P$ACTIVE_P$ACTIVE") (pintype "bidirectional"))
      (node (ref "R6") (pin "2") (pinfunction "2_2") (pintype "passive"))
    )
    (net (code "48") (name "Net-(LCD-LED_K-PadP$11)") (class "Default")
      (node (ref "LCD") (pin "P$11") (pinfunction "LED_K_P$11") (pintype "bidirectional"))
      (node (ref "LCD") (pin "P$12") (pinfunction "LED_K_P$12") (pintype "bidirectional"))
      (node (ref "LCD") (pin "P$13") (pinfunction "LED_K_P$13") (pintype "bidirectional"))
      (node (ref "LCD") (pin "P$14") (pinfunction "LED_K_P$14") (pintype "bidirectional"))
      (node (ref "R23") (pin "1") (pinfunction "1_1") (pintype "passive"))
    )
    (net (code "49") (name "Net-(LED-PadA)") (class "Default")
      (node (ref "LED") (pin "A") (pinfunction "A_A") (pintype "passive"))
      (node (ref "R19") (pin "2") (pinfunction "2_2") (pintype "passive"))
    )
    (net (code "50") (name "Net-(Q1-C)") (class "Default")
      (node (ref "Q1") (pin "3") (pinfunction "C_3") (pintype "passive"))
      (node (ref "R23") (pin "2") (pinfunction "2_2") (pintype "passive"))
    )
    (net (code "51") (name "Net-(Q2-PadB)") (class "Default")
      (node (ref "Q2") (pin "B") (pinfunction "B_B") (pintype "passive"))
      (node (ref "R33") (pin "2") (pinfunction "2_2") (pintype "passive"))
    )
    (net (code "52") (name "Net-(Q4-S)") (class "Default")
      (node (ref "C4") (pin "1") (pinfunction "1_1") (pintype "passive"))
      (node (ref "D2") (pin "C") (pinfunction "C_C") (pintype "passive"))
      (node (ref "Q4") (pin "2") (pinfunction "S_2") (pintype "passive"))
      (node (ref "VREG") (pin "1") (pinfunction "IN_1") (pintype "bidirectional"))
    )
    (net (code "53") (name "Net-(Q5-B)") (class "Default")
      (node (ref "Q5") (pin "1") (pinfunction "B_1") (pintype "passive"))
      (node (ref "R17") (pin "2") (pinfunction "2_2") (pintype "passive"))
    )
    (net (code "54") (name "Net-(Q6-B)") (class "Default")
      (node (ref "Q6") (pin "1") (pinfunction "B_1") (pintype "passive"))
      (node (ref "R18") (pin "2") (pinfunction "2_2") (pintype "passive"))
    )
    (net (code "55") (name "Net-(R8-Pad1)") (class "Default")
      (node (ref "R8") (pin "1") (pinfunction "1_1") (pintype "passive"))
      (node (ref "RIGHT") (pin "P$ACTIVE") (pinfunction "P$ACTIVE_P$ACTIVE") (pintype "bidirectional"))
    )
    (net (code "56") (name "Net-(SPEAKER-+)") (class "Default")
      (node (ref "JACK") (pin "6") (pinfunction "6_6") (pintype "bidirectional"))
      (node (ref "SPEAKER") (pin "2") (pinfunction "+_2") (pintype "passive"))
    )
    (net (code "57") (name "Net-(U$1-PROG)") (class "Default")
      (node (ref "R14") (pin "1") (pinfunction "1_1") (pintype "passive"))
      (node (ref "U$1") (pin "5") (pinfunction "PROG_5") (pintype "input"))
    )
    (net (code "58") (name "Net-(U$1-STAT)") (class "Default")
      (node (ref "R13") (pin "2") (pinfunction "2_2") (pintype "passive"))
      (node (ref "U$1") (pin "1") (pinfunction "STAT_1") (pintype "output"))
    )
    (net (code "59") (name "Net-(U2-GAIN)") (class "Default")
      (node (ref "R2") (pin "1") (pinfunction "1_1") (pintype "passive"))
      (node (ref "U2") (pin "2") (pinfunction "GAIN_2") (pintype "bidirectional"))
    )
    (net (code "60") (name "Net-(USB-C-CC1)") (class "Default")
      (node (ref "R15") (pin "1") (pinfunction "1_1") (pintype "passive"))
      (node (ref "USB-C") (pin "A5") (pinfunction "CC1_A5") (pintype "passive"))
    )
    (net (code "61") (name "Net-(USB-C-CC2)") (class "Default")
      (node (ref "R16") (pin "1") (pinfunction "1_1") (pintype "passive"))
      (node (ref "USB-C") (pin "B5") (pinfunction "CC2_B5") (pintype "passive"))
    )
    (net (code "62") (name "Net-(USB-C-D1+)") (class "Default")
      (node (ref "R29") (pin "1") (pinfunction "1_1") (pintype "passive"))
      (node (ref "USB-C") (pin "A6") (pinfunction "D1+_A6") (pintype "passive"))
      (node (ref "USB-C") (pin "B6") (pinfunction "D2+_B6") (pintype "passive"))
    )
    (net (code "63") (name "Net-(USB-C-D1-)") (class "Default")
      (node (ref "R28") (pin "1") (pinfunction "1_1") (pintype "passive"))
      (node (ref "USB-C") (pin "A7") (pinfunction "D1-_A7") (pintype "passive"))
      (node (ref "USB-C") (pin "B7") (pinfunction "D2-_B7") (pintype "passive"))
    )
    (net (code "64") (name "VBAT") (class "Default")
      (node (ref "BATTERY") (pin "2") (pinfunction "+_2") (pintype "passive"))
      (node (ref "C10") (pin "1") (pinfunction "1_1") (pintype "passive"))
      (node (ref "Q4") (pin "3") (pinfunction "D_3") (pintype "passive"))
      (node (ref "R10") (pin "2") (pinfunction "2_2") (pintype "passive"))
      (node (ref "U$1") (pin "3") (pinfunction "VBAT_3") (pintype "power_in"))
    )
    (net (code "65") (name "VBUS") (class "Default")
      (node (ref "4093DT") (pin "14") (pinfunction "VDD_14") (pintype "power_in"))
      (node (ref "C1") (pin "1") (pinfunction "1_1") (pintype "passive"))
      (node (ref "CHG_LED") (pin "A") (pinfunction "A_A") (pintype "passive"))
      (node (ref "CP2104") (pin "8") (pinfunction "VBUS_8") (pintype "power_in"))
      (node (ref "D2") (pin "A") (pinfunction "A_A") (pintype "passive"))
      (node (ref "Q3") (pin "2") (pinfunction "S_2") (pintype "passive"))
      (node (ref "Q4") (pin "1") (pinfunction "G_1") (pintype "passive"))
      (node (ref "R25") (pin "1") (pinfunction "1_1") (pintype "passive"))
      (node (ref "U$1") (pin "4") (pinfunction "VIN_4") (pintype "power_in"))
      (node (ref "USB-C") (pin "A4") (pinfunction "VBUS_A4") (pintype "passive"))
      (node (ref "USB-C") (pin "A9") (pinfunction "VBUS_A9") (pintype "passive"))
      (node (ref "USB-C") (pin "B4") (pinfunction "VBUS_B4") (pintype "passive"))
      (node (ref "USB-C") (pin "B9") (pinfunction "VBUS_B9") (pintype "passive"))
    )
    (net (code "66") (name "unconnected-(4093DTA-O-Pad3)") (class "Default")
      (node (ref "4093DT") (pin "3") (pinfunction "O_3") (pintype "output"))
    )
    (net (code "67") (name "unconnected-(4093DTB-O-Pad4)") (class "Default")
      (node (ref "4093DT") (pin "4") (pinfunction "O_4") (pintype "output"))
    )
    (net (code "68") (name "unconnected-(CP2104A-#RST-Pad9)") (class "Default")
      (node (ref "CP2104") (pin "9") (pinfunction "#RST_9") (pintype "bidirectional"))
    )
    (net (code "69") (name "unconnected-(CP2104A-#SUSPEND-Pad15)") (class "Default")
      (node (ref "CP2104") (pin "15") (pinfunction "#SUSPEND_15") (pintype "output"))
    )
    (net (code "70") (name "unconnected-(CP2104A-CTS-Pad18)") (class "Default")
      (node (ref "CP2104") (pin "18") (pinfunction "CTS_18") (pintype "input"))
    )
    (net (code "71") (name "unconnected-(CP2104A-DCD-Pad24)") (class "Default")
      (node (ref "CP2104") (pin "24") (pinfunction "DCD_24") (pintype "input"))
    )
    (net (code "72") (name "unconnected-(CP2104A-DSR-Pad22)") (class "Default")
      (node (ref "CP2104") (pin "22") (pinfunction "DSR_22") (pintype "input"))
    )
    (net (code "73") (name "unconnected-(CP2104A-GPIO0{slash}TXLED-Pad14)") (class "Default")
      (node (ref "CP2104") (pin "14") (pinfunction "GPIO0/TXLED_14") (pintype "bidirectional"))
    )
    (net (code "74") (name "unconnected-(CP2104A-GPIO1{slash}RXLED-Pad13)") (class "Default")
      (node (ref "CP2104") (pin "13") (pinfunction "GPIO1/RXLED_13") (pintype "bidirectional"))
    )
    (net (code "75") (name "unconnected-(CP2104A-GPIO2-Pad12)") (class "Default")
      (node (ref "CP2104") (pin "12") (pinfunction "GPIO2_12") (pintype "bidirectional"))
    )
    (net (code "76") (name "unconnected-(CP2104A-GPIO3-Pad11)") (class "Default")
      (node (ref "CP2104") (pin "11") (pinfunction "GPIO3_11") (pintype "bidirectional"))
    )
    (net (code "77") (name "unconnected-(CP2104A-NC-Pad10)") (class "Default")
      (node (ref "CP2104") (pin "10") (pinfunction "NC_10") (pintype "no_connect"))
    )
    (net (code "78") (name "unconnected-(CP2104A-RI-Pad1)") (class "Default")
      (node (ref "CP2104") (pin "1") (pinfunction "RI_1") (pintype "input"))
    )
    (net (code "79") (name "unconnected-(CP2104A-SUSPEND-Pad17)") (class "Default")
      (node (ref "CP2104") (pin "17") (pinfunction "SUSPEND_17") (pintype "output"))
    )
    (net (code "80") (name "unconnected-(CP2104A-VPP-Pad16)") (class "Default")
      (node (ref "CP2104") (pin "16") (pinfunction "VPP_16") (pintype "bidirectional"))
    )
    (net (code "81") (name "unconnected-(ESP32-CLK-Pad20)") (class "Default")
      (node (ref "ESP32") (pin "20") (pinfunction "CLK_20") (pintype "bidirectional"))
    )
    (net (code "82") (name "unconnected-(ESP32-CMD-Pad19)") (class "Default")
      (node (ref "ESP32") (pin "19") (pinfunction "CMD_19") (pintype "bidirectional"))
    )
    (net (code "83") (name "unconnected-(ESP32-NC-Pad27)") (class "Default")
      (node (ref "ESP32") (pin "27") (pinfunction "NC_27") (pintype "bidirectional"))
    )
    (net (code "84") (name "unconnected-(ESP32-NC-Pad28)") (class "Default")
      (node (ref "ESP32") (pin "28") (pinfunction "NC_28") (pintype "bidirectional"))
    )
    (net (code "85") (name "unconnected-(ESP32-NC-Pad32)") (class "Default")
      (node (ref "ESP32") (pin "32") (pinfunction "NC_32") (pintype "bidirectional"))
    )
    (net (code "86") (name "unconnected-(ESP32-SD0-Pad21)") (class "Default")
      (node (ref "ESP32") (pin "21") (pinfunction "SD0_21") (pintype "bidirectional"))
    )
    (net (code "87") (name "unconnected-(ESP32-SD1-Pad22)") (class "Default")
      (node (ref "ESP32") (pin "22") (pinfunction "SD1_22") (pintype "bidirectional"))
    )
    (net (code "88") (name "unconnected-(ESP32-SD2-Pad17)") (class "Default")
      (node (ref "ESP32") (pin "17") (pinfunction "SD2_17") (pintype "bidirectional"))
    )
    (net (code "89") (name "unconnected-(ESP32-SD3-Pad18)") (class "Default")
      (node (ref "ESP32") (pin "18") (pinfunction "SD3_18") (pintype "bidirectional"))
    )
    (net (code "90") (name "unconnected-(JACK-Pad2)") (class "Default")
      (node (ref "JACK") (pin "2") (pinfunction "2_2") (pintype "bidirectional"))
    )
    (net (code "91") (name "unconnected-(JACK-Pad4)") (class "Default")
      (node (ref "JACK") (pin "4") (pinfunction "4_4") (pintype "bidirectional"))
    )
    (net (code "92") (name "unconnected-(LCD-XL-PadP$15)") (class "Default")
      (node (ref "LCD") (pin "P$15") (pinfunction "XL_P$15") (pintype "bidirectional"))
    )
    (net (code "93") (name "unconnected-(LCD-XR-PadP$16)") (class "Default")
      (node (ref "LCD") (pin "P$16") (pinfunction "XR_P$16") (pintype "bidirectional"))
    )
    (net (code "94") (name "unconnected-(LCD-YD-PadP$17)") (class "Default")
      (node (ref "LCD") (pin "P$17") (pinfunction "YD_P$17") (pintype "bidirectional"))
    )
    (net (code "95") (name "unconnected-(LCD-YU-PadP$18)") (class "Default")
      (node (ref "LCD") (pin "P$18") (pinfunction "YU_P$18") (pintype "bidirectional"))
    )
    (net (code "96") (name "unconnected-(R33-Pad1)") (class "Default")
      (node (ref "R33") (pin "1") (pinfunction "1_1") (pintype "passive"))
    )
    (net (code "97") (name "unconnected-(SD_CARD-PadCD)") (class "Default")
      (node (ref "SD_CARD") (pin "CD") (pinfunction "CD_CD") (pintype "bidirectional"))
    )
    (net (code "98") (name "unconnected-(SD_CARD-PadDAT1)") (class "Default")
      (node (ref "SD_CARD") (pin "DAT1") (pinfunction "DAT1_DAT1") (pintype "bidirectional"))
    )
    (net (code "99") (name "unconnected-(SD_CARD-PadDAT2)") (class "Default")
      (node (ref "SD_CARD") (pin "DAT2") (pinfunction "DAT2_DAT2") (pintype "bidirectional"))
    )
    (net (code "100") (name "unconnected-(USB-C-SBU1-PadA8)") (class "Default")
      (node (ref "USB-C") (pin "A8") (pinfunction "SBU1_A8") (pintype "passive"))
    )
    (net (code "101") (name "unconnected-(USB-C-SBU2-PadB8)") (class "Default")
      (node (ref "USB-C") (pin "B8") (pinfunction "SBU2_B8") (pintype "passive"))
    )
    (net (code "102") (name "unconnected-(VREG-P4-Pad4)") (class "Default")
      (node (ref "VREG") (pin "4") (pinfunction "P4_4") (pintype "bidirectional"))
    )
  )
)
